# 04_PSoC6.net
KiCad netlist of a schematic drawn in Altium Designer
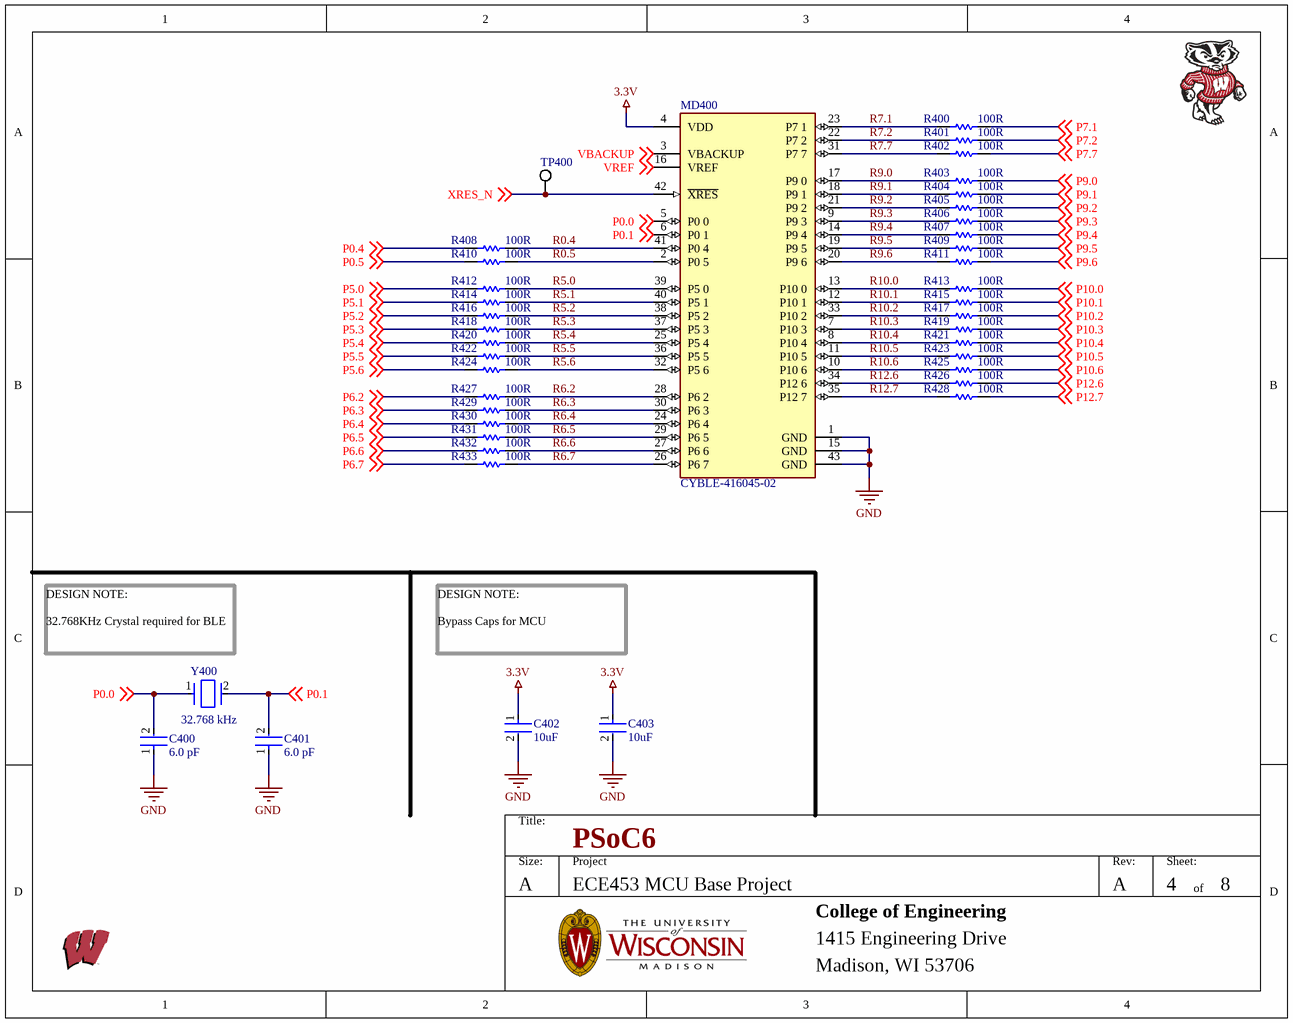
[diagram p0: 04_PSoC6.SchDoc]

(export (version "E")
  (design (tool "Eeschema 10.0.6"))
  (components
    (comp (ref "C400")
      (value "6.0 pF")
      (footprint "FP-CBR08C-MFG")
      (description "CAP CER 6PF 250V C0G/NP0 0805")
      (fields
        (field (name "MANUFACTURER PART NUMBER") "CBR08C609CAGAC")
        (field (name "OCTOPART") "https://octopart.com/cbr08c609cagac-kemet-23841672")
      )
      (libsource (lib "Altium Content Vault") (part "11868f565c42a9108669ba33697ecf6"))
    )
    (comp (ref "C401")
      (value "6.0 pF")
      (footprint "FP-CBR08C-MFG")
      (description "CAP CER 6PF 250V C0G/NP0 0805")
      (fields
        (field (name "MANUFACTURER PART NUMBER") "CBR08C609CAGAC")
        (field (name "OCTOPART") "https://octopart.com/cbr08c609cagac-kemet-23841672")
      )
      (libsource (lib "Altium Content Vault") (part "11868f565c42a9108669ba33697ecf6"))
    )
    (comp (ref "C402")
      (value "10uF")
      (footprint "FP-C0805C-DG-MFG")
      (description "CAP CER 10UF 10V X5R 0805")
      (fields (field (name "TOLERANCE") "10%") (field (name "MANUFACTURER PART NUMBER") "C0805C106K8PACTU"))
      (libsource (lib "Altium Content Vault") (part "11868f565c42a9108669ba33697ecf6"))
    )
    (comp (ref "C403")
      (value "10uF")
      (footprint "FP-C0805C-DG-MFG")
      (description "CAP CER 10UF 10V X5R 0805")
      (fields (field (name "TOLERANCE") "10%") (field (name "MANUFACTURER PART NUMBER") "C0805C106K8PACTU"))
      (libsource (lib "Altium Content Vault") (part "11868f565c42a9108669ba33697ecf6"))
    )
    (comp (ref "MD400")
      (value "CYBLE-416045-02")
      (footprint "FP-CYBLE-416045-02-MFG")
      (description "RF TXRX MOD BLUETOOTH TRACE ANT")
      (fields
        (field (name "OCTOPART") "https://octopart.com/cyble-416045-02-cypress+semiconductor-96386825")
        (field (name "MANUFACTURER") "Cypress Semiconductor")
      )
      (libsource (lib "Altium Content Vault") (part "10a29a4e77099fbb6f911efb04878b1"))
    )
    (comp (ref "R400")
      (value "100R")
      (footprint "RESC2013X60X40ML20T25")
      (fields (field (name "MANUFACTURER") "Panasonic") (field (name "PART NUMBER") "ERA6AEB101V"))
      (libsource (lib "Altium Content Vault") (part "RES"))
    )
    (comp (ref "R401")
      (value "100R")
      (footprint "RESC2013X60X40ML20T25")
      (fields (field (name "MANUFACTURER") "Panasonic") (field (name "PART NUMBER") "ERA6AEB101V"))
      (libsource (lib "Altium Content Vault") (part "RES"))
    )
    (comp (ref "R402")
      (value "100R")
      (footprint "RESC2013X60X40ML20T25")
      (fields (field (name "MANUFACTURER") "Panasonic") (field (name "PART NUMBER") "ERA6AEB101V"))
      (libsource (lib "Altium Content Vault") (part "RES"))
    )
    (comp (ref "R403")
      (value "100R")
      (footprint "RESC2013X60X40ML20T25")
      (fields (field (name "MANUFACTURER") "Panasonic") (field (name "PART NUMBER") "ERA6AEB101V"))
      (libsource (lib "Altium Content Vault") (part "RES"))
    )
    (comp (ref "R404")
      (value "100R")
      (footprint "RESC2013X60X40ML20T25")
      (fields (field (name "MANUFACTURER") "Panasonic") (field (name "PART NUMBER") "ERA6AEB101V"))
      (libsource (lib "Altium Content Vault") (part "RES"))
    )
    (comp (ref "R405")
      (value "100R")
      (footprint "RESC2013X60X40ML20T25")
      (fields (field (name "MANUFACTURER") "Panasonic") (field (name "PART NUMBER") "ERA6AEB101V"))
      (libsource (lib "Altium Content Vault") (part "RES"))
    )
    (comp (ref "R406")
      (value "100R")
      (footprint "RESC2013X60X40ML20T25")
      (fields (field (name "MANUFACTURER") "Panasonic") (field (name "PART NUMBER") "ERA6AEB101V"))
      (libsource (lib "Altium Content Vault") (part "RES"))
    )
    (comp (ref "R407")
      (value "100R")
      (footprint "RESC2013X60X40ML20T25")
      (fields (field (name "MANUFACTURER") "Panasonic") (field (name "PART NUMBER") "ERA6AEB101V"))
      (libsource (lib "Altium Content Vault") (part "RES"))
    )
    (comp (ref "R408")
      (value "100R")
      (footprint "RESC2013X60X40ML20T25")
      (fields (field (name "MANUFACTURER") "Panasonic") (field (name "PART NUMBER") "ERA6AEB101V"))
      (libsource (lib "Altium Content Vault") (part "RES"))
    )
    (comp (ref "R409")
      (value "100R")
      (footprint "RESC2013X60X40ML20T25")
      (fields (field (name "MANUFACTURER") "Panasonic") (field (name "PART NUMBER") "ERA6AEB101V"))
      (libsource (lib "Altium Content Vault") (part "RES"))
    )
    (comp (ref "R410")
      (value "100R")
      (footprint "RESC2013X60X40ML20T25")
      (fields (field (name "MANUFACTURER") "Panasonic") (field (name "PART NUMBER") "ERA6AEB101V"))
      (libsource (lib "Altium Content Vault") (part "RES"))
    )
    (comp (ref "R411")
      (value "100R")
      (footprint "RESC2013X60X40ML20T25")
      (fields (field (name "MANUFACTURER") "Panasonic") (field (name "PART NUMBER") "ERA6AEB101V"))
      (libsource (lib "Altium Content Vault") (part "RES"))
    )
    (comp (ref "R412")
      (value "100R")
      (footprint "RESC2013X60X40ML20T25")
      (fields (field (name "MANUFACTURER") "Panasonic") (field (name "PART NUMBER") "ERA6AEB101V"))
      (libsource (lib "Altium Content Vault") (part "RES"))
    )
    (comp (ref "R413")
      (value "100R")
      (footprint "RESC2013X60X40ML20T25")
      (fields (field (name "MANUFACTURER") "Panasonic") (field (name "PART NUMBER") "ERA6AEB101V"))
      (libsource (lib "Altium Content Vault") (part "RES"))
    )
    (comp (ref "R414")
      (value "100R")
      (footprint "RESC2013X60X40ML20T25")
      (fields (field (name "MANUFACTURER") "Panasonic") (field (name "PART NUMBER") "ERA6AEB101V"))
      (libsource (lib "Altium Content Vault") (part "RES"))
    )
    (comp (ref "R415")
      (value "100R")
      (footprint "RESC2013X60X40ML20T25")
      (fields (field (name "MANUFACTURER") "Panasonic") (field (name "PART NUMBER") "ERA6AEB101V"))
      (libsource (lib "Altium Content Vault") (part "RES"))
    )
    (comp (ref "R416")
      (value "100R")
      (footprint "RESC2013X60X40ML20T25")
      (fields (field (name "MANUFACTURER") "Panasonic") (field (name "PART NUMBER") "ERA6AEB101V"))
      (libsource (lib "Altium Content Vault") (part "RES"))
    )
    (comp (ref "R417")
      (value "100R")
      (footprint "RESC2013X60X40ML20T25")
      (fields (field (name "MANUFACTURER") "Panasonic") (field (name "PART NUMBER") "ERA6AEB101V"))
      (libsource (lib "Altium Content Vault") (part "RES"))
    )
    (comp (ref "R418")
      (value "100R")
      (footprint "RESC2013X60X40ML20T25")
      (fields (field (name "MANUFACTURER") "Panasonic") (field (name "PART NUMBER") "ERA6AEB101V"))
      (libsource (lib "Altium Content Vault") (part "RES"))
    )
    (comp (ref "R419")
      (value "100R")
      (footprint "RESC2013X60X40ML20T25")
      (fields (field (name "MANUFACTURER") "Panasonic") (field (name "PART NUMBER") "ERA6AEB101V"))
      (libsource (lib "Altium Content Vault") (part "RES"))
    )
    (comp (ref "R420")
      (value "100R")
      (footprint "RESC2013X60X40ML20T25")
      (fields (field (name "MANUFACTURER") "Panasonic") (field (name "PART NUMBER") "ERA6AEB101V"))
      (libsource (lib "Altium Content Vault") (part "RES"))
    )
    (comp (ref "R421")
      (value "100R")
      (footprint "RESC2013X60X40ML20T25")
      (fields (field (name "MANUFACTURER") "Panasonic") (field (name "PART NUMBER") "ERA6AEB101V"))
      (libsource (lib "Altium Content Vault") (part "RES"))
    )
    (comp (ref "R422")
      (value "100R")
      (footprint "RESC2013X60X40ML20T25")
      (fields (field (name "MANUFACTURER") "Panasonic") (field (name "PART NUMBER") "ERA6AEB101V"))
      (libsource (lib "Altium Content Vault") (part "RES"))
    )
    (comp (ref "R423")
      (value "100R")
      (footprint "RESC2013X60X40ML20T25")
      (fields (field (name "MANUFACTURER") "Panasonic") (field (name "PART NUMBER") "ERA6AEB101V"))
      (libsource (lib "Altium Content Vault") (part "RES"))
    )
    (comp (ref "R424")
      (value "100R")
      (footprint "RESC2013X60X40ML20T25")
      (fields (field (name "MANUFACTURER") "Panasonic") (field (name "PART NUMBER") "ERA6AEB101V"))
      (libsource (lib "Altium Content Vault") (part "RES"))
    )
    (comp (ref "R425")
      (value "100R")
      (footprint "RESC2013X60X40ML20T25")
      (fields (field (name "MANUFACTURER") "Panasonic") (field (name "PART NUMBER") "ERA6AEB101V"))
      (libsource (lib "Altium Content Vault") (part "RES"))
    )
    (comp (ref "R426")
      (value "100R")
      (footprint "RESC2013X60X40ML20T25")
      (fields (field (name "MANUFACTURER") "Panasonic") (field (name "PART NUMBER") "ERA6AEB101V"))
      (libsource (lib "Altium Content Vault") (part "RES"))
    )
    (comp (ref "R427")
      (value "100R")
      (footprint "RESC2013X60X40ML20T25")
      (fields (field (name "MANUFACTURER") "Panasonic") (field (name "PART NUMBER") "ERA6AEB101V"))
      (libsource (lib "Altium Content Vault") (part "RES"))
    )
    (comp (ref "R428")
      (value "100R")
      (footprint "RESC2013X60X40ML20T25")
      (fields (field (name "MANUFACTURER") "Panasonic") (field (name "PART NUMBER") "ERA6AEB101V"))
      (libsource (lib "Altium Content Vault") (part "RES"))
    )
    (comp (ref "R429")
      (value "100R")
      (footprint "RESC2013X60X40ML20T25")
      (fields (field (name "MANUFACTURER") "Panasonic") (field (name "PART NUMBER") "ERA6AEB101V"))
      (libsource (lib "Altium Content Vault") (part "RES"))
    )
    (comp (ref "R430")
      (value "100R")
      (footprint "RESC2013X60X40ML20T25")
      (fields (field (name "MANUFACTURER") "Panasonic") (field (name "PART NUMBER") "ERA6AEB101V"))
      (libsource (lib "Altium Content Vault") (part "RES"))
    )
    (comp (ref "R431")
      (value "100R")
      (footprint "RESC2013X60X40ML20T25")
      (fields (field (name "MANUFACTURER") "Panasonic") (field (name "PART NUMBER") "ERA6AEB101V"))
      (libsource (lib "Altium Content Vault") (part "RES"))
    )
    (comp (ref "R432")
      (value "100R")
      (footprint "RESC2013X60X40ML20T25")
      (fields (field (name "MANUFACTURER") "Panasonic") (field (name "PART NUMBER") "ERA6AEB101V"))
      (libsource (lib "Altium Content Vault") (part "RES"))
    )
    (comp (ref "R433")
      (value "100R")
      (footprint "RESC2013X60X40ML20T25")
      (fields (field (name "MANUFACTURER") "Panasonic") (field (name "PART NUMBER") "ERA6AEB101V"))
      (libsource (lib "Altium Content Vault") (part "RES"))
    )
    (comp (ref "TP400")
      (value "~")
      (footprint "KSTN-5019_V")
      (description "Test Point, 1 Position SMD, RoHS, Tape and Reel")
      (libsource (lib "Altium Content Vault") (part "TESTPOINT_WHITE"))
    )
    (comp (ref "Y400")
      (value "32.768 kHz")
      (footprint "FP-ABS07-120-MFG")
      (description "CRYSTAL 32.7680KHZ 6PF SMD")
      (fields (field (name "TOLERANCE") "20ppm"))
      (libsource (lib "Altium Content Vault") (part "c23a69dc6c9e2f18f2079038eb95dd1"))
    )
  )
  (nets
    (net (code "1") (name "/R0.4") (class "Default")
      (node (ref "MD400") (pin "41") (pinfunction "P0_4_41") (pintype "bidirectional"))
      (node (ref "R408") (pin "2") (pinfunction "2_2") (pintype "passive"))
    )
    (net (code "2") (name "/R0.5") (class "Default")
      (node (ref "MD400") (pin "2") (pinfunction "P0_5_2") (pintype "bidirectional"))
      (node (ref "R410") (pin "2") (pinfunction "2_2") (pintype "passive"))
    )
    (net (code "3") (name "/R5.0") (class "Default")
      (node (ref "MD400") (pin "39") (pinfunction "P5_0_39") (pintype "bidirectional"))
      (node (ref "R412") (pin "2") (pinfunction "2_2") (pintype "passive"))
    )
    (net (code "4") (name "/R5.1") (class "Default")
      (node (ref "MD400") (pin "40") (pinfunction "P5_1_40") (pintype "bidirectional"))
      (node (ref "R414") (pin "2") (pinfunction "2_2") (pintype "passive"))
    )
    (net (code "5") (name "/R5.2") (class "Default")
      (node (ref "MD400") (pin "38") (pinfunction "P5_2_38") (pintype "bidirectional"))
      (node (ref "R416") (pin "2") (pinfunction "2_2") (pintype "passive"))
    )
    (net (code "6") (name "/R5.3") (class "Default")
      (node (ref "MD400") (pin "37") (pinfunction "P5_3_37") (pintype "bidirectional"))
      (node (ref "R418") (pin "2") (pinfunction "2_2") (pintype "passive"))
    )
    (net (code "7") (name "/R5.4") (class "Default")
      (node (ref "MD400") (pin "25") (pinfunction "P5_4_25") (pintype "bidirectional"))
      (node (ref "R420") (pin "2") (pinfunction "2_2") (pintype "passive"))
    )
    (net (code "8") (name "/R5.5") (class "Default")
      (node (ref "MD400") (pin "36") (pinfunction "P5_5_36") (pintype "bidirectional"))
      (node (ref "R422") (pin "2") (pinfunction "2_2") (pintype "passive"))
    )
    (net (code "9") (name "/R5.6") (class "Default")
      (node (ref "MD400") (pin "32") (pinfunction "P5_6_32") (pintype "bidirectional"))
      (node (ref "R424") (pin "2") (pinfunction "2_2") (pintype "passive"))
    )
    (net (code "10") (name "/R6.2") (class "Default")
      (node (ref "MD400") (pin "28") (pinfunction "P6_2_28") (pintype "bidirectional"))
      (node (ref "R427") (pin "2") (pinfunction "2_2") (pintype "passive"))
    )
    (net (code "11") (name "/R6.3") (class "Default")
      (node (ref "MD400") (pin "30") (pinfunction "P6_3_30") (pintype "bidirectional"))
      (node (ref "R429") (pin "2") (pinfunction "2_2") (pintype "passive"))
    )
    (net (code "12") (name "/R6.4") (class "Default")
      (node (ref "MD400") (pin "24") (pinfunction "P6_4_24") (pintype "bidirectional"))
      (node (ref "R430") (pin "2") (pinfunction "2_2") (pintype "passive"))
    )
    (net (code "13") (name "/R6.5") (class "Default")
      (node (ref "MD400") (pin "29") (pinfunction "P6_5_29") (pintype "bidirectional"))
      (node (ref "R431") (pin "2") (pinfunction "2_2") (pintype "passive"))
    )
    (net (code "14") (name "/R6.6") (class "Default")
      (node (ref "MD400") (pin "27") (pinfunction "P6_6_27") (pintype "bidirectional"))
      (node (ref "R432") (pin "2") (pinfunction "2_2") (pintype "passive"))
    )
    (net (code "15") (name "/R6.7") (class "Default")
      (node (ref "MD400") (pin "26") (pinfunction "P6_7_26") (pintype "bidirectional"))
      (node (ref "R433") (pin "2") (pinfunction "2_2") (pintype "passive"))
    )
    (net (code "16") (name "/R7.1") (class "Default")
      (node (ref "MD400") (pin "23") (pinfunction "P7_1_23") (pintype "bidirectional"))
      (node (ref "R400") (pin "1") (pinfunction "1_1") (pintype "passive"))
    )
    (net (code "17") (name "/R7.2") (class "Default")
      (node (ref "MD400") (pin "22") (pinfunction "P7_2_22") (pintype "bidirectional"))
      (node (ref "R401") (pin "1") (pinfunction "1_1") (pintype "passive"))
    )
    (net (code "18") (name "/R7.7") (class "Default")
      (node (ref "MD400") (pin "31") (pinfunction "P7_7_31") (pintype "bidirectional"))
      (node (ref "R402") (pin "1") (pinfunction "1_1") (pintype "passive"))
    )
    (net (code "19") (name "/R9.0") (class "Default")
      (node (ref "MD400") (pin "17") (pinfunction "P9_0_17") (pintype "bidirectional"))
      (node (ref "R403") (pin "1") (pinfunction "1_1") (pintype "passive"))
    )
    (net (code "20") (name "/R9.1") (class "Default")
      (node (ref "MD400") (pin "18") (pinfunction "P9_1_18") (pintype "bidirectional"))
      (node (ref "R404") (pin "1") (pinfunction "1_1") (pintype "passive"))
    )
    (net (code "21") (name "/R9.2") (class "Default")
      (node (ref "MD400") (pin "21") (pinfunction "P9_2_21") (pintype "bidirectional"))
      (node (ref "R405") (pin "1") (pinfunction "1_1") (pintype "passive"))
    )
    (net (code "22") (name "/R9.3") (class "Default")
      (node (ref "MD400") (pin "9") (pinfunction "P9_3_9") (pintype "bidirectional"))
      (node (ref "R406") (pin "1") (pinfunction "1_1") (pintype "passive"))
    )
    (net (code "23") (name "/R9.4") (class "Default")
      (node (ref "MD400") (pin "14") (pinfunction "P9_4_14") (pintype "bidirectional"))
      (node (ref "R407") (pin "1") (pinfunction "1_1") (pintype "passive"))
    )
    (net (code "24") (name "/R9.5") (class "Default")
      (node (ref "MD400") (pin "19") (pinfunction "P9_5_19") (pintype "bidirectional"))
      (node (ref "R409") (pin "1") (pinfunction "1_1") (pintype "passive"))
    )
    (net (code "25") (name "/R9.6") (class "Default")
      (node (ref "MD400") (pin "20") (pinfunction "P9_6_20") (pintype "bidirectional"))
      (node (ref "R411") (pin "1") (pinfunction "1_1") (pintype "passive"))
    )
    (net (code "26") (name "/R10.0") (class "Default")
      (node (ref "MD400") (pin "13") (pinfunction "P10_0_13") (pintype "bidirectional"))
      (node (ref "R413") (pin "1") (pinfunction "1_1") (pintype "passive"))
    )
    (net (code "27") (name "/R10.1") (class "Default")
      (node (ref "MD400") (pin "12") (pinfunction "P10_1_12") (pintype "bidirectional"))
      (node (ref "R415") (pin "1") (pinfunction "1_1") (pintype "passive"))
    )
    (net (code "28") (name "/R10.2") (class "Default")
      (node (ref "MD400") (pin "33") (pinfunction "P10_2_33") (pintype "bidirectional"))
      (node (ref "R417") (pin "1") (pinfunction "1_1") (pintype "passive"))
    )
    (net (code "29") (name "/R10.3") (class "Default")
      (node (ref "MD400") (pin "7") (pinfunction "P10_3_7") (pintype "bidirectional"))
      (node (ref "R419") (pin "1") (pinfunction "1_1") (pintype "passive"))
    )
    (net (code "30") (name "/R10.4") (class "Default")
      (node (ref "MD400") (pin "8") (pinfunction "P10_4_8") (pintype "bidirectional"))
      (node (ref "R421") (pin "1") (pinfunction "1_1") (pintype "passive"))
    )
    (net (code "31") (name "/R10.5") (class "Default")
      (node (ref "MD400") (pin "11") (pinfunction "P10_5_11") (pintype "bidirectional"))
      (node (ref "R423") (pin "1") (pinfunction "1_1") (pintype "passive"))
    )
    (net (code "32") (name "/R10.6") (class "Default")
      (node (ref "MD400") (pin "10") (pinfunction "P10_6_10") (pintype "bidirectional"))
      (node (ref "R425") (pin "1") (pinfunction "1_1") (pintype "passive"))
    )
    (net (code "33") (name "/R12.6") (class "Default")
      (node (ref "MD400") (pin "34") (pinfunction "P12_6_34") (pintype "bidirectional"))
      (node (ref "R426") (pin "1") (pinfunction "1_1") (pintype "passive"))
    )
    (net (code "34") (name "/R12.7") (class "Default")
      (node (ref "MD400") (pin "35") (pinfunction "P12_7_35") (pintype "bidirectional"))
      (node (ref "R428") (pin "1") (pinfunction "1_1") (pintype "passive"))
    )
    (net (code "35") (name "3.3V") (class "Default")
      (node (ref "C402") (pin "1") (pinfunction "1_1") (pintype "passive"))
      (node (ref "C403") (pin "1") (pinfunction "1_1") (pintype "passive"))
      (node (ref "MD400") (pin "4") (pinfunction "VDD_4") (pintype "power_in"))
    )
    (net (code "36") (name "GND") (class "Default")
      (node (ref "C400") (pin "1") (pinfunction "1_1") (pintype "passive"))
      (node (ref "C401") (pin "1") (pinfunction "1_1") (pintype "passive"))
      (node (ref "C402") (pin "2") (pinfunction "2_2") (pintype "passive"))
      (node (ref "C403") (pin "2") (pinfunction "2_2") (pintype "passive"))
      (node (ref "MD400") (pin "1") (pinfunction "GND_1") (pintype "power_in"))
      (node (ref "MD400") (pin "15") (pinfunction "GND_15") (pintype "power_in"))
      (node (ref "MD400") (pin "43") (pinfunction "GND_43") (pintype "power_in"))
    )
    (net (code "37") (name "P0.0") (class "Default")
      (node (ref "C400") (pin "2") (pinfunction "2_2") (pintype "passive"))
      (node (ref "MD400") (pin "5") (pinfunction "P0_0_5") (pintype "bidirectional"))
      (node (ref "Y400") (pin "1") (pinfunction "1_1") (pintype "passive"))
    )
    (net (code "38") (name "P0.1") (class "Default")
      (node (ref "C401") (pin "2") (pinfunction "2_2") (pintype "passive"))
      (node (ref "MD400") (pin "6") (pinfunction "P0_1_6") (pintype "bidirectional"))
      (node (ref "Y400") (pin "2") (pinfunction "2_2") (pintype "passive"))
    )
    (net (code "39") (name "P0.4") (class "Default")
      (node (ref "R408") (pin "1") (pinfunction "1_1") (pintype "passive"))
    )
    (net (code "40") (name "P0.5") (class "Default")
      (node (ref "R410") (pin "1") (pinfunction "1_1") (pintype "passive"))
    )
    (net (code "41") (name "P5.0") (class "Default")
      (node (ref "R412") (pin "1") (pinfunction "1_1") (pintype "passive"))
    )
    (net (code "42") (name "P5.1") (class "Default")
      (node (ref "R414") (pin "1") (pinfunction "1_1") (pintype "passive"))
    )
    (net (code "43") (name "P5.2") (class "Default")
      (node (ref "R416") (pin "1") (pinfunction "1_1") (pintype "passive"))
    )
    (net (code "44") (name "P5.3") (class "Default")
      (node (ref "R418") (pin "1") (pinfunction "1_1") (pintype "passive"))
    )
    (net (code "45") (name "P5.4") (class "Default")
      (node (ref "R420") (pin "1") (pinfunction "1_1") (pintype "passive"))
    )
    (net (code "46") (name "P5.5") (class "Default")
      (node (ref "R422") (pin "1") (pinfunction "1_1") (pintype "passive"))
    )
    (net (code "47") (name "P5.6") (class "Default")
      (node (ref "R424") (pin "1") (pinfunction "1_1") (pintype "passive"))
    )
    (net (code "48") (name "P6.2") (class "Default")
      (node (ref "R427") (pin "1") (pinfunction "1_1") (pintype "passive"))
    )
    (net (code "49") (name "P6.3") (class "Default")
      (node (ref "R429") (pin "1") (pinfunction "1_1") (pintype "passive"))
    )
    (net (code "50") (name "P6.4") (class "Default")
      (node (ref "R430") (pin "1") (pinfunction "1_1") (pintype "passive"))
    )
    (net (code "51") (name "P6.5") (class "Default")
      (node (ref "R431") (pin "1") (pinfunction "1_1") (pintype "passive"))
    )
    (net (code "52") (name "P6.6") (class "Default")
      (node (ref "R432") (pin "1") (pinfunction "1_1") (pintype "passive"))
    )
    (net (code "53") (name "P6.7") (class "Default")
      (node (ref "R433") (pin "1") (pinfunction "1_1") (pintype "passive"))
    )
    (net (code "54") (name "P7.1") (class "Default")
      (node (ref "R400") (pin "2") (pinfunction "2_2") (pintype "passive"))
    )
    (net (code "55") (name "P7.2") (class "Default")
      (node (ref "R401") (pin "2") (pinfunction "2_2") (pintype "passive"))
    )
    (net (code "56") (name "P7.7") (class "Default")
      (node (ref "R402") (pin "2") (pinfunction "2_2") (pintype "passive"))
    )
    (net (code "57") (name "P9.0") (class "Default")
      (node (ref "R403") (pin "2") (pinfunction "2_2") (pintype "passive"))
    )
    (net (code "58") (name "P9.1") (class "Default")
      (node (ref "R404") (pin "2") (pinfunction "2_2") (pintype "passive"))
    )
    (net (code "59") (name "P9.2") (class "Default")
      (node (ref "R405") (pin "2") (pinfunction "2_2") (pintype "passive"))
    )
    (net (code "60") (name "P9.3") (class "Default")
      (node (ref "R406") (pin "2") (pinfunction "2_2") (pintype "passive"))
    )
    (net (code "61") (name "P9.4") (class "Default")
      (node (ref "R407") (pin "2") (pinfunction "2_2") (pintype "passive"))
    )
    (net (code "62") (name "P9.5") (class "Default")
      (node (ref "R409") (pin "2") (pinfunction "2_2") (pintype "passive"))
    )
    (net (code "63") (name "P9.6") (class "Default")
      (node (ref "R411") (pin "2") (pinfunction "2_2") (pintype "passive"))
    )
    (net (code "64") (name "P10.0") (class "Default")
      (node (ref "R413") (pin "2") (pinfunction "2_2") (pintype "passive"))
    )
    (net (code "65") (name "P10.1") (class "Default")
      (node (ref "R415") (pin "2") (pinfunction "2_2") (pintype "passive"))
    )
    (net (code "66") (name "P10.2") (class "Default")
      (node (ref "R417") (pin "2") (pinfunction "2_2") (pintype "passive"))
    )
    (net (code "67") (name "P10.3") (class "Default")
      (node (ref "R419") (pin "2") (pinfunction "2_2") (pintype "passive"))
    )
    (net (code "68") (name "P10.4") (class "Default")
      (node (ref "R421") (pin "2") (pinfunction "2_2") (pintype "passive"))
    )
    (net (code "69") (name "P10.5") (class "Default")
      (node (ref "R423") (pin "2") (pinfunction "2_2") (pintype "passive"))
    )
    (net (code "70") (name "P10.6") (class "Default")
      (node (ref "R425") (pin "2") (pinfunction "2_2") (pintype "passive"))
    )
    (net (code "71") (name "P12.6") (class "Default")
      (node (ref "R426") (pin "2") (pinfunction "2_2") (pintype "passive"))
    )
    (net (code "72") (name "P12.7") (class "Default")
      (node (ref "R428") (pin "2") (pinfunction "2_2") (pintype "passive"))
    )
    (net (code "73") (name "VBACKUP") (class "Default")
      (node (ref "MD400") (pin "3") (pinfunction "VBACKUP_3") (pintype "power_in"))
    )
    (net (code "74") (name "VREF") (class "Default")
      (node (ref "MD400") (pin "16") (pinfunction "VREF_16") (pintype "power_in"))
    )
    (net (code "75") (name "XRES_N") (class "Default")
      (node (ref "MD400") (pin "42") (pinfunction "~{XRES}_42") (pintype "input"))
      (node (ref "TP400") (pin "1") (pinfunction "1_1") (pintype "passive"))
    )
  )
)
